# ChargeControlBoard.net
KiCad netlist of a schematic drawn in Altium Designer
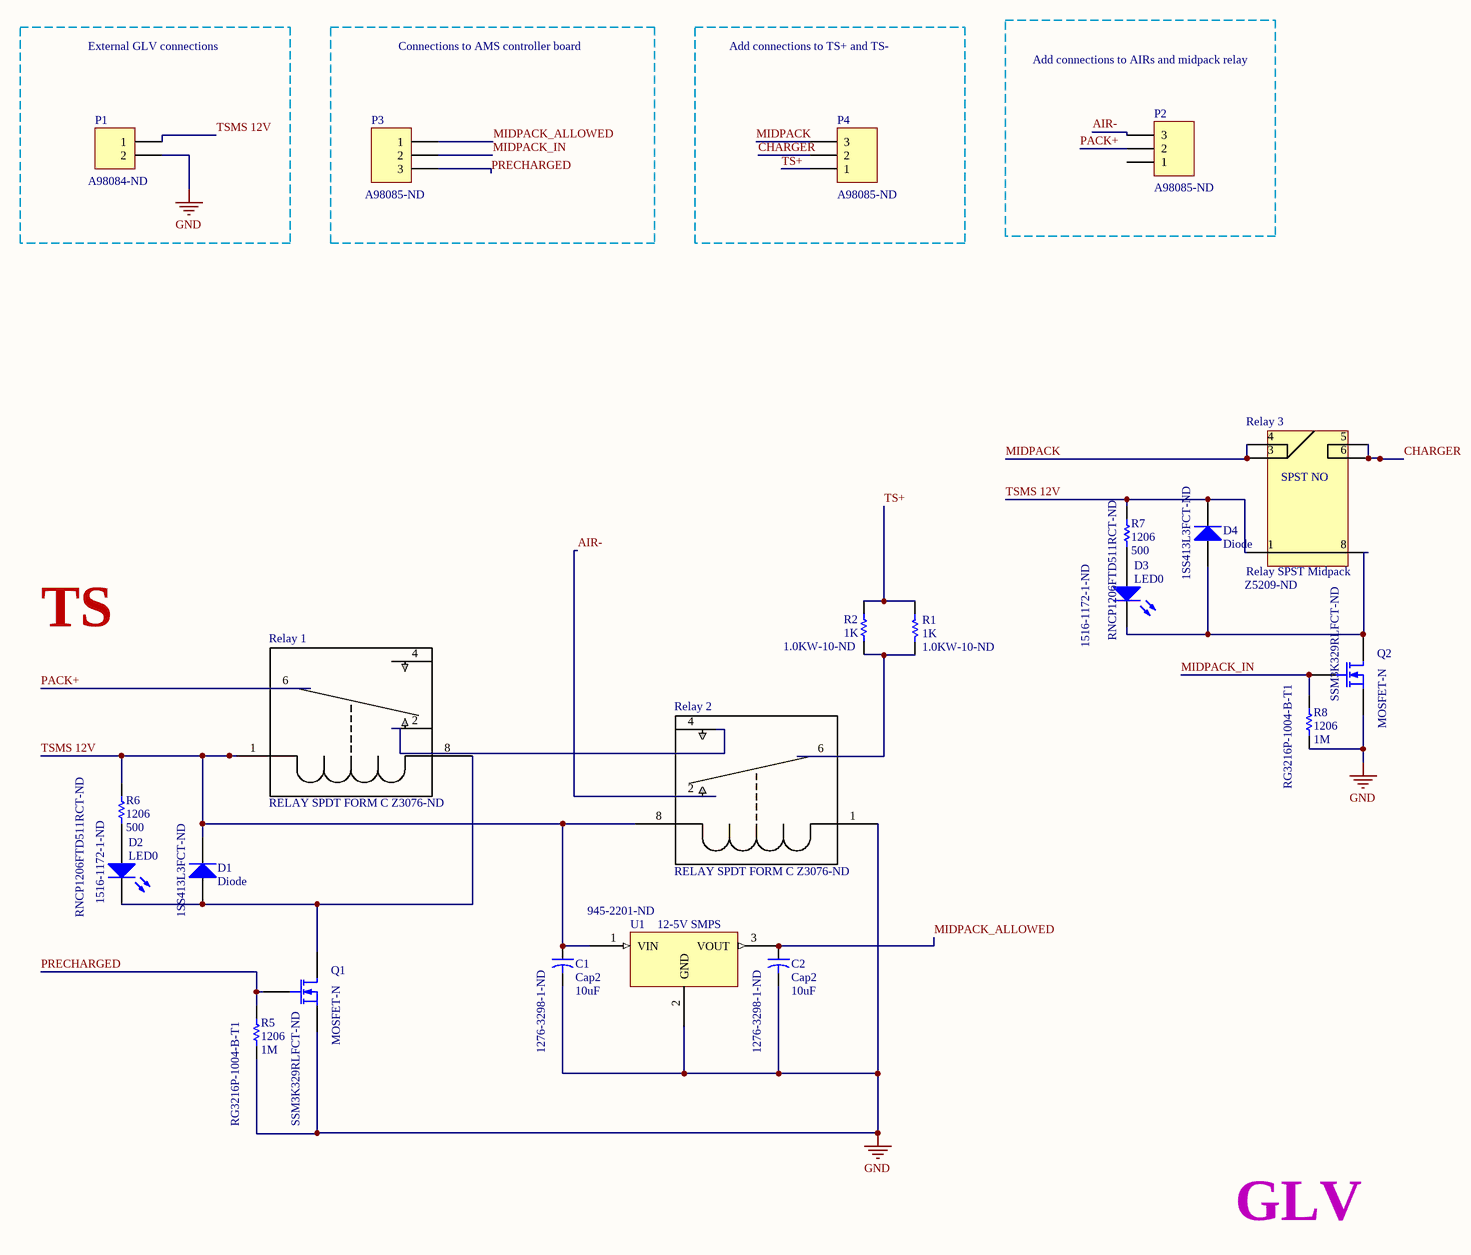
[diagram p0: ChargeControlBoard.SchDoc]

(export (version "E")
  (design (tool "Eeschema 10.0.6"))
  (components
    (comp (ref "C1")
      (value "Cap2")
      (footprint "1206")
      (description "Capacitor")
      (fields
        (field (name "ALTIUM_VALUE") "10uF")
        (field (name "SUPPLIER PART NUMBER 1") "1276-3298-1-ND")
        (field (name "PUBLISHER") "Altium Limited")
      )
      (libsource (lib "Miscellaneous Devices") (part "Cap2"))
    )
    (comp (ref "C2")
      (value "Cap2")
      (footprint "1206")
      (description "Capacitor")
      (fields
        (field (name "ALTIUM_VALUE") "10uF")
        (field (name "SUPPLIER PART NUMBER 1") "1276-3298-1-ND")
        (field (name "PUBLISHER") "Altium Limited")
      )
      (libsource (lib "Miscellaneous Devices") (part "Cap2"))
    )
    (comp (ref "D1")
      (value "Diode")
      (footprint "DIODE SODFL100X48-2N")
      (description "Switching diode")
      (fields
        (field (name "SUPPLIER PART NUMBER 1") "1SS413L3FCT-ND")
        (field (name "PUBLISHER") "Altium Limited")
      )
      (libsource (lib "Miscellaneous Devices") (part "Diode"))
    )
    (comp (ref "D2")
      (value "LED0")
      (footprint "C1206")
      (description "Typical INFRARED GaAs LED")
      (fields
        (field (name "SUPPLIER PART NUMBER 1") "1516-1172-1-ND")
        (field (name "PUBLISHER") "Altium Limited")
      )
      (libsource (lib "Miscellaneous Devices") (part "LED0"))
    )
    (comp (ref "D3")
      (value "LED0")
      (footprint "C1206")
      (description "Typical INFRARED GaAs LED")
      (fields
        (field (name "SUPPLIER PART NUMBER 1") "1516-1172-1-ND")
        (field (name "PUBLISHER") "Altium Limited")
      )
      (libsource (lib "Miscellaneous Devices") (part "LED0"))
    )
    (comp (ref "D4")
      (value "Diode")
      (footprint "DIODE SODFL100X48-2N")
      (description "Switching diode")
      (fields
        (field (name "SUPPLIER PART NUMBER 1") "1SS413L3FCT-ND")
        (field (name "PUBLISHER") "Altium Limited")
      )
      (libsource (lib "Miscellaneous Devices") (part "Diode"))
    )
    (comp (ref "P1")
      (value "Header 2")
      (footprint "2 Pos wire to board")
      (description "Header, 2-Pin")
      (fields (field (name "SUPPLIER PART NUMBER") "A98084-ND") (field (name "PUBLISHER") "Altium Limited"))
      (libsource (lib "Miscellaneous Connectors") (part "Header 2"))
    )
    (comp (ref "P2")
      (value "Header 3")
      (footprint "3 Pos wire to board")
      (description "Header, 3-Pin")
      (fields (field (name "SUPPLIER PART NUMBER") "A98085-ND") (field (name "PUBLISHER") "Altium Limited"))
      (libsource (lib "Miscellaneous Connectors") (part "Header 3"))
    )
    (comp (ref "P3")
      (value "Header 3")
      (footprint "3 Pos wire to board")
      (description "Header, 3-Pin")
      (fields (field (name "SUPPLIER PART NUMBER") "A98085-ND") (field (name "PUBLISHER") "Altium Limited"))
      (libsource (lib "") (part "Header 3_1"))
    )
    (comp (ref "P4")
      (value "Header 3")
      (footprint "3 Pos wire to board")
      (description "Header, 3-Pin")
      (fields (field (name "SUPPLIER PART NUMBER") "A98085-ND") (field (name "PUBLISHER") "Altium Limited"))
      (libsource (lib "Miscellaneous Connectors") (part "Header 3"))
    )
    (comp (ref "Q1")
      (value "MOSFET-N")
      (footprint "SOT23")
      (description "N-Channel MOSFET")
      (fields
        (field (name "SUPPLIER PART NUMBER 1") "SSM3K329RLFCT-ND")
        (field (name "PUBLISHER") "Altium Limited")
      )
      (libsource (lib "Miscellaneous Devices") (part "MOSFET-N"))
    )
    (comp (ref "Q2")
      (value "MOSFET-N")
      (footprint "SOT23")
      (description "N-Channel MOSFET")
      (fields
        (field (name "SUPPLIER PART NUMBER 1") "SSM3K329RLFCT-ND")
        (field (name "PUBLISHER") "Altium Limited")
      )
      (libsource (lib "Miscellaneous Devices") (part "MOSFET-N"))
    )
    (comp (ref "R1")
      (value "1K")
      (footprint "Res 1k 10W")
      (description "Resistor")
      (fields
        (field (name "SUPPLIER PART NUMBER") "1.0KW-10-ND")
        (field (name "Comment") "Res1")
        (field (name "PUBLISHER") "Altium Limited")
      )
      (libsource (lib "Miscellaneous Devices") (part "Res1"))
    )
    (comp (ref "R2")
      (value "1K")
      (footprint "Res 1k 10W")
      (description "Resistor")
      (fields
        (field (name "SUPPLIER PART NUMBER") "1.0KW-10-ND")
        (field (name "Comment") "Res1")
        (field (name "PUBLISHER") "Altium Limited")
      )
      (libsource (lib "Miscellaneous Devices") (part "Res1"))
    )
    (comp (ref "R5")
      (value "1206")
      (footprint "1206 (High Density)")
      (description "Resistor")
      (fields
        (field (name "ALTIUM_VALUE") "1M")
        (field (name "SUPPLIER PART NUMBER 1") "RG3216P-1004-B-T1")
        (field (name "PUBLISHER") "Altium Limited")
      )
      (libsource (lib "Miscellaneous Devices") (part "Res1"))
    )
    (comp (ref "R6")
      (value "1206")
      (footprint "C1206")
      (description "Resistor")
      (fields
        (field (name "ALTIUM_VALUE") "500")
        (field (name "SUPPLIER PART NUMBER 1") "RNCP1206FTD511RCT-ND")
        (field (name "PUBLISHER") "Altium Limited")
      )
      (libsource (lib "Miscellaneous Devices") (part "Res1"))
    )
    (comp (ref "R7")
      (value "1206")
      (footprint "C1206")
      (description "Resistor")
      (fields
        (field (name "ALTIUM_VALUE") "500")
        (field (name "SUPPLIER PART NUMBER 1") "RNCP1206FTD511RCT-ND")
        (field (name "PUBLISHER") "Altium Limited")
      )
      (libsource (lib "Miscellaneous Devices") (part "Res1"))
    )
    (comp (ref "R8")
      (value "1206")
      (footprint "1206 (High Density)")
      (description "Resistor")
      (fields
        (field (name "ALTIUM_VALUE") "1M")
        (field (name "SUPPLIER PART NUMBER 1") "RG3216P-1004-B-T1")
        (field (name "PUBLISHER") "Altium Limited")
      )
      (libsource (lib "Miscellaneous Devices") (part "Res1"))
    )
    (comp (ref "Relay 1")
      (value "RELAY SPDT FORM C Z3076-ND")
      (footprint "RELAY SPDT FORM C Z3076-ND")
      (libsource (lib "UVICHybridLibrary") (part "RELAY SPDT FORM C Z3076-ND"))
    )
    (comp (ref "Relay 2")
      (value "RELAY SPDT FORM C Z3076-ND")
      (footprint "RELAY SPDT FORM C Z3076-ND")
      (libsource (lib "") (part "RELAY SPDT FORM C Z3076-ND_1"))
    )
    (comp (ref "Relay 3")
      (value "Relay SPST Midpack")
      (footprint "Relay SPDT NO MIDPACK")
      (fields (field (name "SUPPLIER PART NUMBER 1") "Z5209-ND"))
      (libsource (lib "UVICHybridLibrary") (part "Relay SPST Midpack"))
    )
    (comp (ref "U1")
      (value "12-5V SMPS")
      (footprint "Rr-788E5")
      (fields (field (name "SUPPLIER PART NUMBER 1") "945-2201-ND"))
      (libsource (lib "Power_Supplies") (part "Component_1"))
    )
  )
  (nets
    (net (code "1") (name "/AIR-") (class "Default")
      (node (ref "P2") (pin "3") (pinfunction "3_3") (pintype "passive"))
      (node (ref "Relay 2") (pin "2") (pinfunction "4_2") (pintype "passive"))
    )
    (net (code "2") (name "/CHARGER") (class "Default")
      (node (ref "P4") (pin "2") (pinfunction "2_2") (pintype "passive"))
      (node (ref "Relay 3") (pin "5") (pintype "passive"))
      (node (ref "Relay 3") (pin "6") (pintype "passive"))
    )
    (net (code "3") (name "/MIDPACK") (class "Default")
      (node (ref "P4") (pin "3") (pinfunction "3_3") (pintype "passive"))
      (node (ref "Relay 3") (pin "3") (pintype "passive"))
      (node (ref "Relay 3") (pin "4") (pintype "passive"))
    )
    (net (code "4") (name "/MIDPACK_ALLOWED") (class "Default")
      (node (ref "C2") (pin "1") (pinfunction "1_1") (pintype "passive"))
      (node (ref "P3") (pin "1") (pinfunction "1_1") (pintype "passive"))
      (node (ref "U1") (pin "3") (pinfunction "VOUT_3") (pintype "output"))
    )
    (net (code "5") (name "/MIDPACK_IN") (class "Default")
      (node (ref "P3") (pin "2") (pinfunction "2_2") (pintype "passive"))
      (node (ref "Q2") (pin "2") (pinfunction "G_2") (pintype "passive"))
      (node (ref "R8") (pin "2") (pinfunction "2_2") (pintype "passive"))
    )
    (net (code "6") (name "/PACK+") (class "Default")
      (node (ref "P2") (pin "2") (pinfunction "2_2") (pintype "passive"))
      (node (ref "Relay 1") (pin "6") (pinfunction "2_6") (pintype "passive"))
    )
    (net (code "7") (name "/PRECHARGED") (class "Default")
      (node (ref "P3") (pin "3") (pinfunction "3_3") (pintype "passive"))
      (node (ref "Q1") (pin "2") (pinfunction "G_2") (pintype "passive"))
      (node (ref "R5") (pin "2") (pinfunction "2_2") (pintype "passive"))
    )
    (net (code "8") (name "/TS+") (class "Default")
      (node (ref "P4") (pin "1") (pinfunction "1_1") (pintype "passive"))
      (node (ref "R1") (pin "2") (pinfunction "2_2") (pintype "passive"))
      (node (ref "R2") (pin "2") (pinfunction "2_2") (pintype "passive"))
    )
    (net (code "9") (name "/TSMS 12V") (class "Default")
      (node (ref "C1") (pin "1") (pinfunction "1_1") (pintype "passive"))
      (node (ref "D1") (pin "2") (pinfunction "K_2") (pintype "passive"))
      (node (ref "D4") (pin "2") (pinfunction "K_2") (pintype "passive"))
      (node (ref "P1") (pin "1") (pinfunction "1_1") (pintype "passive"))
      (node (ref "R6") (pin "1") (pinfunction "1_1") (pintype "passive"))
      (node (ref "R7") (pin "1") (pinfunction "1_1") (pintype "passive"))
      (node (ref "Relay 1") (pin "1") (pinfunction "1_1") (pintype "passive"))
      (node (ref "Relay 2") (pin "8") (pinfunction "5_8") (pintype "passive"))
      (node (ref "Relay 3") (pin "1") (pintype "passive"))
      (node (ref "U1") (pin "1") (pinfunction "VIN_1") (pintype "input"))
    )
    (net (code "10") (name "GND") (class "Default")
      (node (ref "C1") (pin "2") (pinfunction "2_2") (pintype "passive"))
      (node (ref "C2") (pin "2") (pinfunction "2_2") (pintype "passive"))
      (node (ref "P1") (pin "2") (pinfunction "2_2") (pintype "passive"))
      (node (ref "Q1") (pin "3") (pinfunction "S_3") (pintype "passive"))
      (node (ref "Q2") (pin "3") (pinfunction "S_3") (pintype "passive"))
      (node (ref "R5") (pin "1") (pinfunction "1_1") (pintype "passive"))
      (node (ref "R8") (pin "1") (pinfunction "1_1") (pintype "passive"))
      (node (ref "Relay 2") (pin "1") (pinfunction "1_1") (pintype "passive"))
      (node (ref "U1") (pin "2") (pinfunction "GND_2") (pintype "passive"))
    )
    (net (code "11") (name "Net-(D1-A)") (class "Default")
      (node (ref "D1") (pin "1") (pinfunction "A_1") (pintype "passive"))
      (node (ref "D2") (pin "2") (pinfunction "K_2") (pintype "passive"))
      (node (ref "Q1") (pin "1") (pinfunction "D_1") (pintype "passive"))
      (node (ref "Relay 1") (pin "8") (pinfunction "5_8") (pintype "passive"))
    )
    (net (code "12") (name "Net-(D2-A)") (class "Default")
      (node (ref "D2") (pin "1") (pinfunction "A_1") (pintype "passive"))
      (node (ref "R6") (pin "2") (pinfunction "2_2") (pintype "passive"))
    )
    (net (code "13") (name "Net-(D3-A)") (class "Default")
      (node (ref "D3") (pin "1") (pinfunction "A_1") (pintype "passive"))
      (node (ref "R7") (pin "2") (pinfunction "2_2") (pintype "passive"))
    )
    (net (code "14") (name "Net-(D3-K)") (class "Default")
      (node (ref "D3") (pin "2") (pinfunction "K_2") (pintype "passive"))
      (node (ref "D4") (pin "1") (pinfunction "A_1") (pintype "passive"))
      (node (ref "Q2") (pin "1") (pinfunction "D_1") (pintype "passive"))
      (node (ref "Relay 3") (pin "8") (pintype "passive"))
    )
    (net (code "15") (name "Net-(Relay 1-4)") (class "Default")
      (node (ref "Relay 1") (pin "2") (pinfunction "4_2") (pintype "passive"))
      (node (ref "Relay 2") (pin "4") (pinfunction "3_4") (pintype "passive"))
    )
    (net (code "16") (name "Net-(Relay 2-2)") (class "Default")
      (node (ref "R1") (pin "1") (pinfunction "1_1") (pintype "passive"))
      (node (ref "R2") (pin "1") (pinfunction "1_1") (pintype "passive"))
      (node (ref "Relay 2") (pin "6") (pinfunction "2_6") (pintype "passive"))
    )
    (net (code "17") (name "unconnected-(P2-Pad1)") (class "Default")
      (node (ref "P2") (pin "1") (pinfunction "1_1") (pintype "passive"))
    )
    (net (code "18") (name "unconnected-(Relay 1-3-Pad4)") (class "Default")
      (node (ref "Relay 1") (pin "4") (pinfunction "3_4") (pintype "passive"))
    )
  )
)
